# stm32__PCB_V1_0.net
KiCad netlist of a schematic drawn in Altium Designer
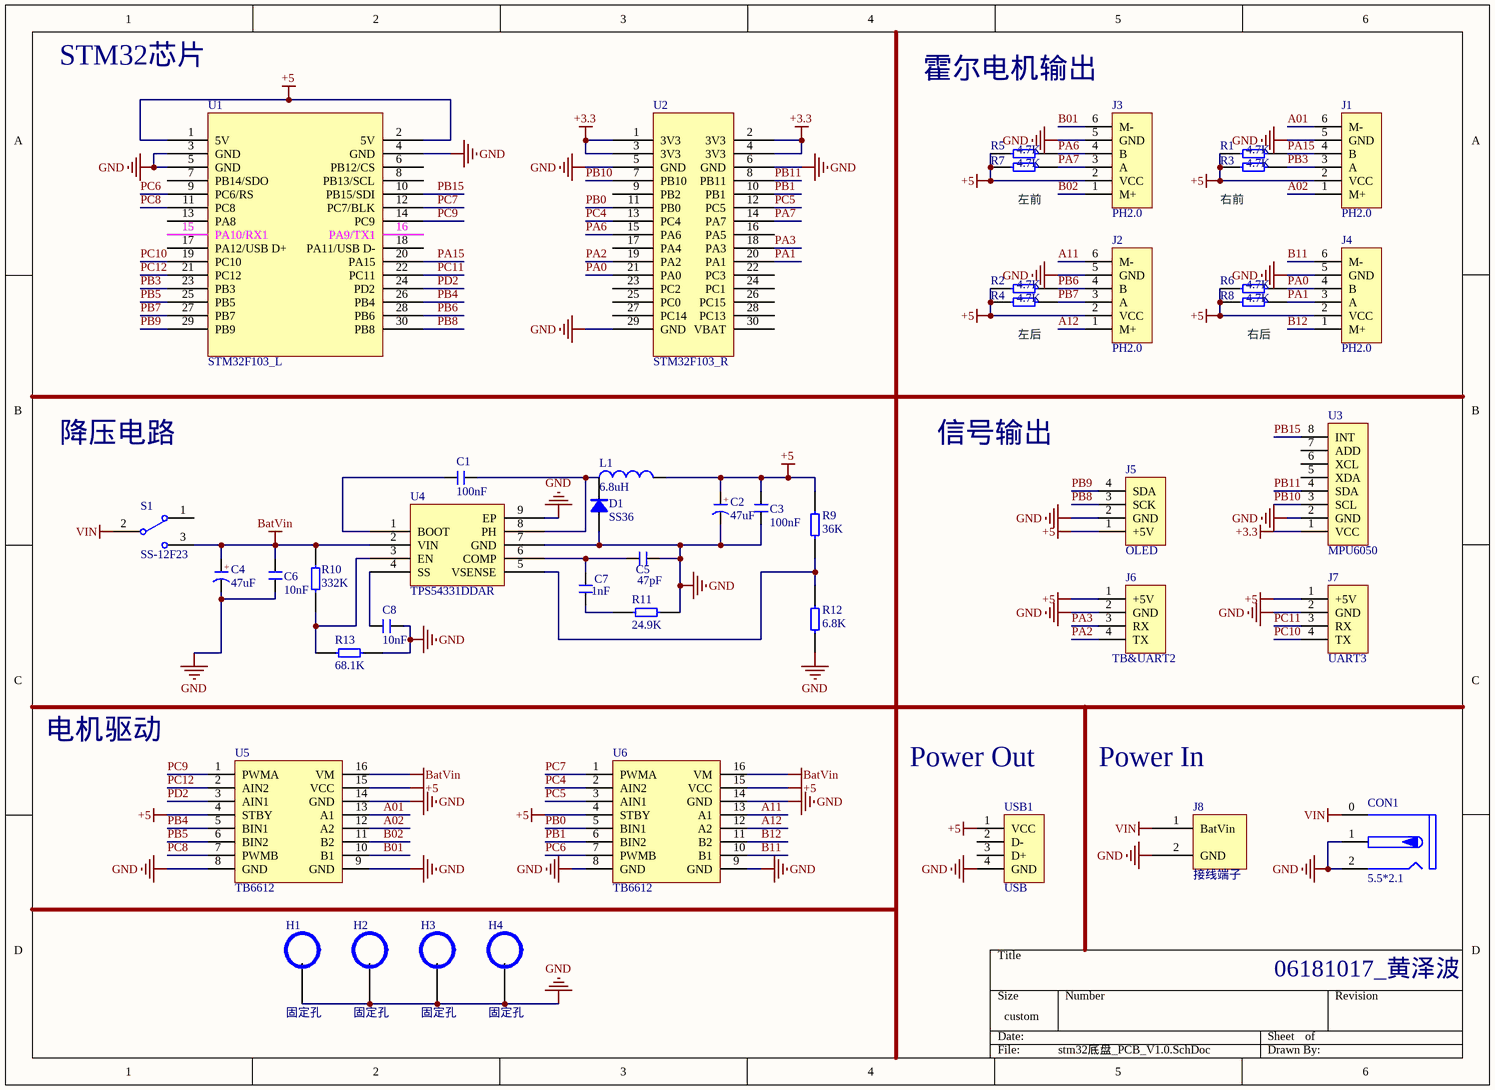
[diagram p0: stm32底盘_PCB_V1.0.SchDoc]

(export (version "E")
  (design (tool "Eeschema 10.0.6"))
  (components
    (comp (ref "C1")
      (value "100nF")
      (footprint "C 0603_L")
      (description "无极性贴片电容")
      (libsource (lib "stm32底盘_PCB_V1.0") (part "C"))
    )
    (comp (ref "C2")
      (value "47uF")
      (footprint "CS 2.5*6.3*7 - C")
      (description "直插固态电容")
      (libsource (lib "stm32底盘_PCB_V1.0") (part "C-CS"))
    )
    (comp (ref "C3")
      (value "100nF")
      (footprint "C 0603_M")
      (description "无极性贴片电容")
      (libsource (lib "stm32底盘_PCB_V1.0") (part "C"))
    )
    (comp (ref "C4")
      (value "47uF")
      (footprint "CS 2.5*6.3*7 - C")
      (description "直插固态电容")
      (libsource (lib "stm32底盘_PCB_V1.0") (part "C-CS"))
    )
    (comp (ref "C5")
      (value "47pF")
      (footprint "C 0603_L")
      (description "无极性贴片电容")
      (libsource (lib "stm32底盘_PCB_V1.0") (part "C"))
    )
    (comp (ref "C6")
      (value "10nF")
      (footprint "C 0603_L")
      (description "无极性贴片电容")
      (libsource (lib "stm32底盘_PCB_V1.0") (part "C"))
    )
    (comp (ref "C7")
      (value "1nF")
      (footprint "C 0603_L")
      (description "无极性贴片电容")
      (libsource (lib "stm32底盘_PCB_V1.0") (part "C"))
    )
    (comp (ref "C8")
      (value "10nF")
      (footprint "C 0603_L")
      (description "无极性贴片电容")
      (libsource (lib "stm32底盘_PCB_V1.0") (part "C"))
    )
    (comp (ref "CON1")
      (value "5.5*2.1")
      (footprint "DC-005")
      (description "带屏蔽DC电源接口")
      (libsource (lib "stm32底盘_PCB_V1.0") (part "DC-005P"))
    )
    (comp (ref "D1")
      (value "SS36")
      (footprint "SMA")
      (description "肖特基二极管")
      (libsource (lib "stm32底盘_PCB_V1.0") (part "SS36"))
    )
    (comp (ref "H1") (value "固定孔") (footprint "铜柱孔") (libsource (lib "stm32底盘_PCB_V1.0") (part "固定孔")))
    (comp (ref "H2") (value "固定孔") (footprint "铜柱孔") (libsource (lib "stm32底盘_PCB_V1.0") (part "固定孔")))
    (comp (ref "H3") (value "固定孔") (footprint "铜柱孔") (libsource (lib "stm32底盘_PCB_V1.0") (part "固定孔")))
    (comp (ref "H4") (value "固定孔") (footprint "铜柱孔") (libsource (lib "stm32底盘_PCB_V1.0") (part "固定孔")))
    (comp (ref "J1")
      (value "PH2.0")
      (footprint "PH2.0-LI-6P")
      (description "6脚接口")
      (libsource (lib "stm32底盘_PCB_V1.0") (part "PH2.0"))
    )
    (comp (ref "J2")
      (value "PH2.0")
      (footprint "PH2.0-LI-6P")
      (description "6脚接口")
      (libsource (lib "stm32底盘_PCB_V1.0") (part "PH2.0"))
    )
    (comp (ref "J3")
      (value "PH2.0")
      (footprint "PH2.0-LI-6P")
      (description "6脚接口")
      (libsource (lib "stm32底盘_PCB_V1.0") (part "PH2.0"))
    )
    (comp (ref "J4")
      (value "PH2.0")
      (footprint "PH2.0-LI-6P")
      (description "6脚接口")
      (libsource (lib "stm32底盘_PCB_V1.0") (part "PH2.0"))
    )
    (comp (ref "J5")
      (value "OLED")
      (footprint "OELD MODULE 1.9")
      (description "IIC")
      (libsource (lib "stm32底盘_PCB_V1.0") (part "OLED"))
    )
    (comp (ref "J6")
      (value "TB&UART2")
      (footprint "TB&UART2")
      (description "串口通信")
      (libsource (lib "stm32底盘_PCB_V1.0") (part "TB&UART2"))
    )
    (comp (ref "J7")
      (value "UART3")
      (footprint "UART3")
      (description "串口通信")
      (libsource (lib "stm32底盘_PCB_V1.0") (part "UART3"))
    )
    (comp (ref "J8")
      (value "接线端子")
      (footprint "KF128-5.08-2P")
      (description "航模电池接口")
      (libsource (lib "stm32底盘_PCB_V1.0") (part "T形接头"))
    )
    (comp (ref "L1")
      (value "6.8uH")
      (footprint "CDRH73")
      (description "小功率贴片电感")
      (libsource (lib "stm32底盘_PCB_V1.0") (part "L"))
    )
    (comp (ref "R1")
      (value "4.7K")
      (footprint "R 0603_M")
      (description "电阻")
      (libsource (lib "stm32底盘_PCB_V1.0") (part "Res"))
    )
    (comp (ref "R2")
      (value "4.7K")
      (footprint "R 0603_M")
      (description "电阻")
      (libsource (lib "stm32底盘_PCB_V1.0") (part "Res"))
    )
    (comp (ref "R3")
      (value "4.7K")
      (footprint "R 0603_M")
      (description "电阻")
      (libsource (lib "stm32底盘_PCB_V1.0") (part "Res"))
    )
    (comp (ref "R4")
      (value "4.7K")
      (footprint "R 0603_M")
      (description "电阻")
      (libsource (lib "stm32底盘_PCB_V1.0") (part "Res"))
    )
    (comp (ref "R5")
      (value "4.7K")
      (footprint "R 0603_M")
      (description "电阻")
      (libsource (lib "stm32底盘_PCB_V1.0") (part "Res"))
    )
    (comp (ref "R6")
      (value "4.7K")
      (footprint "R 0603_M")
      (description "电阻")
      (libsource (lib "stm32底盘_PCB_V1.0") (part "Res"))
    )
    (comp (ref "R7")
      (value "4.7K")
      (footprint "R 0603_M")
      (description "电阻")
      (libsource (lib "stm32底盘_PCB_V1.0") (part "Res"))
    )
    (comp (ref "R8")
      (value "4.7K")
      (footprint "R 0603_M")
      (description "电阻")
      (libsource (lib "stm32底盘_PCB_V1.0") (part "Res"))
    )
    (comp (ref "R9")
      (value "36K")
      (footprint "R 0603_M")
      (description "电阻")
      (libsource (lib "stm32底盘_PCB_V1.0") (part "Res"))
    )
    (comp (ref "R10")
      (value "332K")
      (footprint "R 0603_M")
      (description "电阻")
      (libsource (lib "stm32底盘_PCB_V1.0") (part "Res"))
    )
    (comp (ref "R11")
      (value "24.9K")
      (footprint "R 0603_M")
      (description "电阻")
      (libsource (lib "stm32底盘_PCB_V1.0") (part "Res"))
    )
    (comp (ref "R12")
      (value "6.8K")
      (footprint "R 0603_M")
      (description "电阻")
      (libsource (lib "stm32底盘_PCB_V1.0") (part "Res"))
    )
    (comp (ref "R13")
      (value "68.1K")
      (footprint "R 0603_M")
      (description "电阻")
      (libsource (lib "stm32底盘_PCB_V1.0") (part "Res"))
    )
    (comp (ref "S1")
      (value "SS-12F23")
      (footprint "SS-12D10")
      (description "1路波动开关")
      (libsource (lib "5.1   - 按键-开关") (part "SSW-1P"))
    )
    (comp (ref "U1")
      (value "STM32F103_L")
      (footprint "STM32F103_L")
      (description "32位STM单片机")
      (libsource (lib "stm32底盘_PCB_V1.0") (part "STM32F103_L"))
    )
    (comp (ref "U2")
      (value "STM32F103_R")
      (footprint "STM32F103_R")
      (description "32位STM单片机")
      (libsource (lib "stm32底盘_PCB_V1.0") (part "STM32F103_R"))
    )
    (comp (ref "U3")
      (value "MPU6050")
      (footprint "MPU6050")
      (libsource (lib "stm32底盘_PCB_V1.0") (part "MPU6050"))
    )
    (comp (ref "U4")
      (value "TPS54331DDAR")
      (footprint "SOP8_M")
      (description "压降芯片")
      (libsource (lib "stm32底盘_PCB_V1.0") (part "TPS54331DDAR"))
    )
    (comp (ref "U5")
      (value "TB6612")
      (footprint "TB6612")
      (libsource (lib "stm32底盘_PCB_V1.0") (part "TB6612"))
    )
    (comp (ref "U6")
      (value "TB6612")
      (footprint "TB6612")
      (libsource (lib "stm32底盘_PCB_V1.0") (part "TB6612"))
    )
    (comp (ref "USB1")
      (value "USB")
      (footprint "USB-A/S_A")
      (description "USB-A型母接口")
      (libsource (lib "4.1   - 接口类") (part "USB-A/S"))
    )
  )
  (nets
    (net (code "1") (name "+3.3") (class "Default")
      (node (ref "U2") (pin "1") (pinfunction "3V3_1") (pintype "passive"))
      (node (ref "U2") (pin "2") (pinfunction "3V3_2") (pintype "passive"))
      (node (ref "U2") (pin "3") (pinfunction "3V3_3") (pintype "passive"))
      (node (ref "U2") (pin "4") (pinfunction "3V3_4") (pintype "passive"))
      (node (ref "U3") (pin "1") (pinfunction "VCC_1") (pintype "passive"))
    )
    (net (code "2") (name "+5") (class "Default")
      (node (ref "C2") (pin "1") (pinfunction "A_1") (pintype "passive"))
      (node (ref "C3") (pin "2") (pinfunction "2_2") (pintype "passive"))
      (node (ref "J1") (pin "2") (pinfunction "VCC_2") (pintype "passive"))
      (node (ref "J2") (pin "2") (pinfunction "VCC_2") (pintype "passive"))
      (node (ref "J3") (pin "2") (pinfunction "VCC_2") (pintype "passive"))
      (node (ref "J4") (pin "2") (pinfunction "VCC_2") (pintype "passive"))
      (node (ref "J5") (pin "1") (pinfunction "+5V_1") (pintype "passive"))
      (node (ref "J6") (pin "1") (pinfunction "+5V_1") (pintype "passive"))
      (node (ref "J7") (pin "1") (pinfunction "+5V_1") (pintype "passive"))
      (node (ref "L1") (pin "2") (pinfunction "2_2") (pintype "passive"))
      (node (ref "R1") (pin "1") (pintype "passive"))
      (node (ref "R2") (pin "1") (pintype "passive"))
      (node (ref "R3") (pin "1") (pintype "passive"))
      (node (ref "R4") (pin "1") (pintype "passive"))
      (node (ref "R5") (pin "1") (pintype "passive"))
      (node (ref "R6") (pin "1") (pintype "passive"))
      (node (ref "R7") (pin "1") (pintype "passive"))
      (node (ref "R8") (pin "1") (pintype "passive"))
      (node (ref "R9") (pin "2") (pintype "passive"))
      (node (ref "U1") (pin "1") (pinfunction "5V_1") (pintype "passive"))
      (node (ref "U1") (pin "2") (pinfunction "5V_2") (pintype "passive"))
      (node (ref "U5") (pin "15") (pinfunction "VCC_15") (pintype "passive"))
      (node (ref "U5") (pin "4") (pinfunction "STBY_4") (pintype "passive"))
      (node (ref "U6") (pin "15") (pinfunction "VCC_15") (pintype "passive"))
      (node (ref "U6") (pin "4") (pinfunction "STBY_4") (pintype "passive"))
      (node (ref "USB1") (pin "1") (pinfunction "VCC_1") (pintype "passive"))
    )
    (net (code "3") (name "/A01") (class "Default")
      (node (ref "J1") (pin "6") (pinfunction "M-_6") (pintype "passive"))
      (node (ref "U5") (pin "13") (pinfunction "A1_13") (pintype "passive"))
    )
    (net (code "4") (name "/A02") (class "Default")
      (node (ref "J1") (pin "1") (pinfunction "M+_1") (pintype "passive"))
      (node (ref "U5") (pin "12") (pinfunction "A2_12") (pintype "passive"))
    )
    (net (code "5") (name "/A11") (class "Default")
      (node (ref "J2") (pin "6") (pinfunction "M-_6") (pintype "passive"))
      (node (ref "U6") (pin "13") (pinfunction "A1_13") (pintype "passive"))
    )
    (net (code "6") (name "/A12") (class "Default")
      (node (ref "J2") (pin "1") (pinfunction "M+_1") (pintype "passive"))
      (node (ref "U6") (pin "12") (pinfunction "A2_12") (pintype "passive"))
    )
    (net (code "7") (name "/B01") (class "Default")
      (node (ref "J3") (pin "6") (pinfunction "M-_6") (pintype "passive"))
      (node (ref "U5") (pin "10") (pinfunction "B1_10") (pintype "passive"))
    )
    (net (code "8") (name "/B02") (class "Default")
      (node (ref "J3") (pin "1") (pinfunction "M+_1") (pintype "passive"))
      (node (ref "U5") (pin "11") (pinfunction "B2_11") (pintype "passive"))
    )
    (net (code "9") (name "/B11") (class "Default")
      (node (ref "J4") (pin "6") (pinfunction "M-_6") (pintype "passive"))
      (node (ref "U6") (pin "10") (pinfunction "B1_10") (pintype "passive"))
    )
    (net (code "10") (name "/B12") (class "Default")
      (node (ref "J4") (pin "1") (pinfunction "M+_1") (pintype "passive"))
      (node (ref "U6") (pin "11") (pinfunction "B2_11") (pintype "passive"))
    )
    (net (code "11") (name "/PA0") (class "Default")
      (node (ref "J4") (pin "4") (pinfunction "B_4") (pintype "passive"))
      (node (ref "R6") (pin "2") (pintype "passive"))
      (node (ref "U2") (pin "21") (pinfunction "PA0_21") (pintype "passive"))
    )
    (net (code "12") (name "/PA1") (class "Default")
      (node (ref "J4") (pin "3") (pinfunction "A_3") (pintype "passive"))
      (node (ref "R8") (pin "2") (pintype "passive"))
      (node (ref "U2") (pin "20") (pinfunction "PA1_20") (pintype "passive"))
    )
    (net (code "13") (name "/PA2") (class "Default")
      (node (ref "J6") (pin "4") (pinfunction "TX_4") (pintype "passive"))
      (node (ref "U2") (pin "19") (pinfunction "PA2_19") (pintype "passive"))
    )
    (net (code "14") (name "/PA3") (class "Default")
      (node (ref "J6") (pin "3") (pinfunction "RX_3") (pintype "passive"))
      (node (ref "U2") (pin "18") (pinfunction "PA3_18") (pintype "passive"))
    )
    (net (code "15") (name "/PA6") (class "Default")
      (node (ref "J3") (pin "4") (pinfunction "B_4") (pintype "passive"))
      (node (ref "R5") (pin "2") (pintype "passive"))
      (node (ref "U2") (pin "15") (pinfunction "PA6_15") (pintype "passive"))
    )
    (net (code "16") (name "/PA7") (class "Default")
      (node (ref "J3") (pin "3") (pinfunction "A_3") (pintype "passive"))
      (node (ref "R7") (pin "2") (pintype "passive"))
      (node (ref "U2") (pin "14") (pinfunction "PA7_14") (pintype "passive"))
    )
    (net (code "17") (name "/PA15") (class "Default")
      (node (ref "J1") (pin "4") (pinfunction "B_4") (pintype "passive"))
      (node (ref "R1") (pin "2") (pintype "passive"))
      (node (ref "U1") (pin "20") (pinfunction "PA15_20") (pintype "passive"))
    )
    (net (code "18") (name "/PB0") (class "Default")
      (node (ref "U2") (pin "11") (pinfunction "PB0_11") (pintype "passive"))
      (node (ref "U6") (pin "5") (pinfunction "BIN1_5") (pintype "passive"))
    )
    (net (code "19") (name "/PB1") (class "Default")
      (node (ref "U2") (pin "10") (pinfunction "PB1_10") (pintype "passive"))
      (node (ref "U6") (pin "6") (pinfunction "BIN2_6") (pintype "passive"))
    )
    (net (code "20") (name "/PB3") (class "Default")
      (node (ref "J1") (pin "3") (pinfunction "A_3") (pintype "passive"))
      (node (ref "R3") (pin "2") (pintype "passive"))
      (node (ref "U1") (pin "23") (pinfunction "PB3_23") (pintype "passive"))
    )
    (net (code "21") (name "/PB4") (class "Default")
      (node (ref "U1") (pin "26") (pinfunction "PB4_26") (pintype "passive"))
      (node (ref "U5") (pin "5") (pinfunction "BIN1_5") (pintype "passive"))
    )
    (net (code "22") (name "/PB5") (class "Default")
      (node (ref "U1") (pin "25") (pinfunction "PB5_25") (pintype "passive"))
      (node (ref "U5") (pin "6") (pinfunction "BIN2_6") (pintype "passive"))
    )
    (net (code "23") (name "/PB6") (class "Default")
      (node (ref "J2") (pin "4") (pinfunction "B_4") (pintype "passive"))
      (node (ref "R2") (pin "2") (pintype "passive"))
      (node (ref "U1") (pin "28") (pinfunction "PB6_28") (pintype "passive"))
    )
    (net (code "24") (name "/PB7") (class "Default")
      (node (ref "J2") (pin "3") (pinfunction "A_3") (pintype "passive"))
      (node (ref "R4") (pin "2") (pintype "passive"))
      (node (ref "U1") (pin "27") (pinfunction "PB7_27") (pintype "passive"))
    )
    (net (code "25") (name "/PB8") (class "Default")
      (node (ref "J5") (pin "3") (pinfunction "SCK_3") (pintype "passive"))
      (node (ref "U1") (pin "30") (pinfunction "PB8_30") (pintype "passive"))
    )
    (net (code "26") (name "/PB9") (class "Default")
      (node (ref "J5") (pin "4") (pinfunction "SDA_4") (pintype "passive"))
      (node (ref "U1") (pin "29") (pinfunction "PB9_29") (pintype "passive"))
    )
    (net (code "27") (name "/PB10") (class "Default")
      (node (ref "U2") (pin "7") (pinfunction "PB10_7") (pintype "passive"))
      (node (ref "U3") (pin "3") (pinfunction "SCL_3") (pintype "passive"))
    )
    (net (code "28") (name "/PB11") (class "Default")
      (node (ref "U2") (pin "8") (pinfunction "PB11_8") (pintype "passive"))
      (node (ref "U3") (pin "4") (pinfunction "SDA_4") (pintype "passive"))
    )
    (net (code "29") (name "/PB15") (class "Default")
      (node (ref "U1") (pin "10") (pinfunction "PB15/SDI_10") (pintype "passive"))
      (node (ref "U3") (pin "8") (pinfunction "INT_8") (pintype "passive"))
    )
    (net (code "30") (name "/PC4") (class "Default")
      (node (ref "U2") (pin "13") (pinfunction "PC4_13") (pintype "passive"))
      (node (ref "U6") (pin "2") (pinfunction "AIN2_2") (pintype "passive"))
    )
    (net (code "31") (name "/PC5") (class "Default")
      (node (ref "U2") (pin "12") (pinfunction "PC5_12") (pintype "passive"))
      (node (ref "U6") (pin "3") (pinfunction "AIN1_3") (pintype "passive"))
    )
    (net (code "32") (name "/PC6") (class "Default")
      (node (ref "U1") (pin "9") (pinfunction "PC6/RS_9") (pintype "passive"))
      (node (ref "U6") (pin "7") (pinfunction "PWMB_7") (pintype "passive"))
    )
    (net (code "33") (name "/PC7") (class "Default")
      (node (ref "U1") (pin "12") (pinfunction "PC7/BLK_12") (pintype "passive"))
      (node (ref "U6") (pin "1") (pinfunction "PWMA_1") (pintype "passive"))
    )
    (net (code "34") (name "/PC8") (class "Default")
      (node (ref "U1") (pin "11") (pinfunction "PC8_11") (pintype "passive"))
      (node (ref "U5") (pin "7") (pinfunction "PWMB_7") (pintype "passive"))
    )
    (net (code "35") (name "/PC9") (class "Default")
      (node (ref "U1") (pin "14") (pinfunction "PC9_14") (pintype "passive"))
      (node (ref "U5") (pin "1") (pinfunction "PWMA_1") (pintype "passive"))
    )
    (net (code "36") (name "/PC10") (class "Default")
      (node (ref "J7") (pin "4") (pinfunction "TX_4") (pintype "passive"))
      (node (ref "U1") (pin "19") (pinfunction "PC10_19") (pintype "passive"))
    )
    (net (code "37") (name "/PC11") (class "Default")
      (node (ref "J7") (pin "3") (pinfunction "RX_3") (pintype "passive"))
      (node (ref "U1") (pin "22") (pinfunction "PC11_22") (pintype "passive"))
    )
    (net (code "38") (name "/PC12") (class "Default")
      (node (ref "U1") (pin "21") (pinfunction "PC12_21") (pintype "passive"))
      (node (ref "U5") (pin "2") (pinfunction "AIN2_2") (pintype "passive"))
    )
    (net (code "39") (name "/PD2") (class "Default")
      (node (ref "U1") (pin "24") (pinfunction "PD2_24") (pintype "passive"))
      (node (ref "U5") (pin "3") (pinfunction "AIN1_3") (pintype "passive"))
    )
    (net (code "40") (name "BatVin") (class "Default")
      (node (ref "C4") (pin "1") (pinfunction "A_1") (pintype "passive"))
      (node (ref "C6") (pin "2") (pinfunction "2_2") (pintype "passive"))
      (node (ref "R10") (pin "1") (pintype "passive"))
      (node (ref "S1") (pin "3") (pinfunction "3_3") (pintype "passive"))
      (node (ref "U4") (pin "2") (pinfunction "VIN_2") (pintype "passive"))
      (node (ref "U5") (pin "16") (pinfunction "VM_16") (pintype "passive"))
      (node (ref "U6") (pin "16") (pinfunction "VM_16") (pintype "passive"))
    )
    (net (code "41") (name "GND") (class "Default")
      (node (ref "C2") (pin "2") (pinfunction "K_2") (pintype "passive"))
      (node (ref "C3") (pin "1") (pinfunction "1_1") (pintype "passive"))
      (node (ref "C4") (pin "2") (pinfunction "K_2") (pintype "passive"))
      (node (ref "C5") (pin "1") (pinfunction "1_1") (pintype "passive"))
      (node (ref "C6") (pin "1") (pinfunction "1_1") (pintype "passive"))
      (node (ref "C8") (pin "1") (pinfunction "1_1") (pintype "passive"))
      (node (ref "CON1") (pin "1") (pintype "power_in"))
      (node (ref "CON1") (pin "2") (pintype "power_in"))
      (node (ref "D1") (pin "1") (pinfunction "A_1") (pintype "passive"))
      (node (ref "H1") (pin "11") (pinfunction "11_11") (pintype "passive"))
      (node (ref "H2") (pin "11") (pinfunction "11_11") (pintype "passive"))
      (node (ref "H3") (pin "11") (pinfunction "11_11") (pintype "passive"))
      (node (ref "H4") (pin "11") (pinfunction "11_11") (pintype "passive"))
      (node (ref "J1") (pin "5") (pinfunction "GND_5") (pintype "passive"))
      (node (ref "J2") (pin "5") (pinfunction "GND_5") (pintype "passive"))
      (node (ref "J3") (pin "5") (pinfunction "GND_5") (pintype "passive"))
      (node (ref "J4") (pin "5") (pinfunction "GND_5") (pintype "passive"))
      (node (ref "J5") (pin "2") (pinfunction "GND_2") (pintype "passive"))
      (node (ref "J6") (pin "2") (pinfunction "GND_2") (pintype "passive"))
      (node (ref "J7") (pin "2") (pinfunction "GND_2") (pintype "passive"))
      (node (ref "J8") (pin "2") (pinfunction "GND_2") (pintype "passive"))
      (node (ref "R11") (pin "2") (pintype "passive"))
      (node (ref "R12") (pin "1") (pintype "passive"))
      (node (ref "R13") (pin "2") (pintype "passive"))
      (node (ref "U1") (pin "3") (pinfunction "GND_3") (pintype "passive"))
      (node (ref "U1") (pin "4") (pinfunction "GND_4") (pintype "passive"))
      (node (ref "U1") (pin "5") (pinfunction "GND_5") (pintype "passive"))
      (node (ref "U2") (pin "29") (pinfunction "GND_29") (pintype "passive"))
      (node (ref "U2") (pin "5") (pinfunction "GND_5") (pintype "passive"))
      (node (ref "U2") (pin "6") (pinfunction "GND_6") (pintype "passive"))
      (node (ref "U3") (pin "2") (pinfunction "GND_2") (pintype "passive"))
      (node (ref "U4") (pin "7") (pinfunction "GND_7") (pintype "passive"))
      (node (ref "U4") (pin "9") (pinfunction "EP_9") (pintype "passive"))
      (node (ref "U5") (pin "14") (pinfunction "GND_14") (pintype "passive"))
      (node (ref "U5") (pin "8") (pinfunction "GND_8") (pintype "passive"))
      (node (ref "U5") (pin "9") (pinfunction "GND_9") (pintype "passive"))
      (node (ref "U6") (pin "14") (pinfunction "GND_14") (pintype "passive"))
      (node (ref "U6") (pin "8") (pinfunction "GND_8") (pintype "passive"))
      (node (ref "U6") (pin "9") (pinfunction "GND_9") (pintype "passive"))
      (node (ref "USB1") (pin "4") (pinfunction "GND_4") (pintype "passive"))
    )
    (net (code "42") (name "Net-(C7-Pad1)") (class "Default")
      (node (ref "C7") (pin "1") (pinfunction "1_1") (pintype "passive"))
      (node (ref "R11") (pin "1") (pintype "passive"))
    )
    (net (code "43") (name "Net-(D1-K)") (class "Default")
      (node (ref "C1") (pin "2") (pinfunction "2_2") (pintype "passive"))
      (node (ref "D1") (pin "2") (pinfunction "K_2") (pintype "passive"))
      (node (ref "L1") (pin "1") (pinfunction "1_1") (pintype "passive"))
      (node (ref "U4") (pin "8") (pinfunction "PH_8") (pintype "passive"))
    )
    (net (code "44") (name "Net-(U4-BOOT)") (class "Default")
      (node (ref "C1") (pin "1") (pinfunction "1_1") (pintype "passive"))
      (node (ref "U4") (pin "1") (pinfunction "BOOT_1") (pintype "passive"))
    )
    (net (code "45") (name "Net-(U4-COMP)") (class "Default")
      (node (ref "C5") (pin "2") (pinfunction "2_2") (pintype "passive"))
      (node (ref "C7") (pin "2") (pinfunction "2_2") (pintype "passive"))
      (node (ref "U4") (pin "6") (pinfunction "COMP_6") (pintype "passive"))
    )
    (net (code "46") (name "Net-(U4-EN)") (class "Default")
      (node (ref "R10") (pin "2") (pintype "passive"))
      (node (ref "R13") (pin "1") (pintype "passive"))
      (node (ref "U4") (pin "3") (pinfunction "EN_3") (pintype "passive"))
    )
    (net (code "47") (name "Net-(U4-SS)") (class "Default")
      (node (ref "C8") (pin "2") (pinfunction "2_2") (pintype "passive"))
      (node (ref "U4") (pin "4") (pinfunction "SS_4") (pintype "passive"))
    )
    (net (code "48") (name "Net-(U4-VSENSE)") (class "Default")
      (node (ref "R12") (pin "2") (pintype "passive"))
      (node (ref "R9") (pin "1") (pintype "passive"))
      (node (ref "U4") (pin "5") (pinfunction "VSENSE_5") (pintype "passive"))
    )
    (net (code "49") (name "VIN") (class "Default")
      (node (ref "CON1") (pin "0") (pintype "power_in"))
      (node (ref "J8") (pin "1") (pinfunction "BatVin_1") (pintype "passive"))
      (node (ref "S1") (pin "2") (pinfunction "2_2") (pintype "passive"))
    )
    (net (code "50") (name "unconnected-(S1-Pad1)") (class "Default")
      (node (ref "S1") (pin "1") (pinfunction "1_1") (pintype "passive"))
    )
    (net (code "51") (name "unconnected-(U1-PA8-Pad13)") (class "Default")
      (node (ref "U1") (pin "13") (pinfunction "PA8_13") (pintype "passive"))
    )
    (net (code "52") (name "unconnected-(U1-PA9{slash}TX1-Pad16)") (class "Default")
      (node (ref "U1") (pin "16") (pinfunction "PA9/TX1_16") (pintype "passive"))
    )
    (net (code "53") (name "unconnected-(U1-PA10{slash}RX1-Pad15)") (class "Default")
      (node (ref "U1") (pin "15") (pinfunction "PA10/RX1_15") (pintype "passive"))
    )
    (net (code "54") (name "unconnected-(U1-PA11{slash}USB_D--Pad18)") (class "Default")
      (node (ref "U1") (pin "18") (pinfunction "PA11/USB_D-_18") (pintype "passive"))
    )
    (net (code "55") (name "unconnected-(U1-PA12{slash}USB_D+-Pad17)") (class "Default")
      (node (ref "U1") (pin "17") (pinfunction "PA12/USB_D+_17") (pintype "passive"))
    )
    (net (code "56") (name "unconnected-(U1-PB12{slash}CS-Pad6)") (class "Default")
      (node (ref "U1") (pin "6") (pinfunction "PB12/CS_6") (pintype "passive"))
    )
    (net (code "57") (name "unconnected-(U1-PB13{slash}SCL-Pad8)") (class "Default")
      (node (ref "U1") (pin "8") (pinfunction "PB13/SCL_8") (pintype "passive"))
    )
    (net (code "58") (name "unconnected-(U1-PB14{slash}SDO-Pad7)") (class "Default")
      (node (ref "U1") (pin "7") (pinfunction "PB14/SDO_7") (pintype "passive"))
    )
    (net (code "59") (name "unconnected-(U2-PA4-Pad17)") (class "Default")
      (node (ref "U2") (pin "17") (pinfunction "PA4_17") (pintype "passive"))
    )
    (net (code "60") (name "unconnected-(U2-PA5-Pad16)") (class "Default")
      (node (ref "U2") (pin "16") (pinfunction "PA5_16") (pintype "passive"))
    )
    (net (code "61") (name "unconnected-(U2-PB2-Pad9)") (class "Default")
      (node (ref "U2") (pin "9") (pinfunction "PB2_9") (pintype "passive"))
    )
    (net (code "62") (name "unconnected-(U2-PC0-Pad25)") (class "Default")
      (node (ref "U2") (pin "25") (pinfunction "PC0_25") (pintype "passive"))
    )
    (net (code "63") (name "unconnected-(U2-PC1-Pad24)") (class "Default")
      (node (ref "U2") (pin "24") (pinfunction "PC1_24") (pintype "passive"))
    )
    (net (code "64") (name "unconnected-(U2-PC2-Pad23)") (class "Default")
      (node (ref "U2") (pin "23") (pinfunction "PC2_23") (pintype "passive"))
    )
    (net (code "65") (name "unconnected-(U2-PC3-Pad22)") (class "Default")
      (node (ref "U2") (pin "22") (pinfunction "PC3_22") (pintype "passive"))
    )
    (net (code "66") (name "unconnected-(U2-PC13-Pad28)") (class "Default")
      (node (ref "U2") (pin "28") (pinfunction "PC13_28") (pintype "passive"))
    )
    (net (code "67") (name "unconnected-(U2-PC14-Pad27)") (class "Default")
      (node (ref "U2") (pin "27") (pinfunction "PC14_27") (pintype "passive"))
    )
    (net (code "68") (name "unconnected-(U2-PC15-Pad26)") (class "Default")
      (node (ref "U2") (pin "26") (pinfunction "PC15_26") (pintype "passive"))
    )
    (net (code "69") (name "unconnected-(U2-VBAT-Pad30)") (class "Default")
      (node (ref "U2") (pin "30") (pinfunction "VBAT_30") (pintype "passive"))
    )
    (net (code "70") (name "unconnected-(U3-ADD-Pad7)") (class "Default")
      (node (ref "U3") (pin "7") (pinfunction "ADD_7") (pintype "passive"))
    )
    (net (code "71") (name "unconnected-(U3-XCL-Pad6)") (class "Default")
      (node (ref "U3") (pin "6") (pinfunction "XCL_6") (pintype "passive"))
    )
    (net (code "72") (name "unconnected-(U3-XDA-Pad5)") (class "Default")
      (node (ref "U3") (pin "5") (pinfunction "XDA_5") (pintype "passive"))
    )
    (net (code "73") (name "unconnected-(USB1-D+-Pad3)") (class "Default")
      (node (ref "USB1") (pin "3") (pinfunction "D+_3") (pintype "passive"))
    )
    (net (code "74") (name "unconnected-(USB1-D--Pad2)") (class "Default")
      (node (ref "USB1") (pin "2") (pinfunction "D-_2") (pintype "passive"))
    )
  )
)
